# ekomigacz_3R.net
KiCad netlist of a schematic drawn in EAGLE
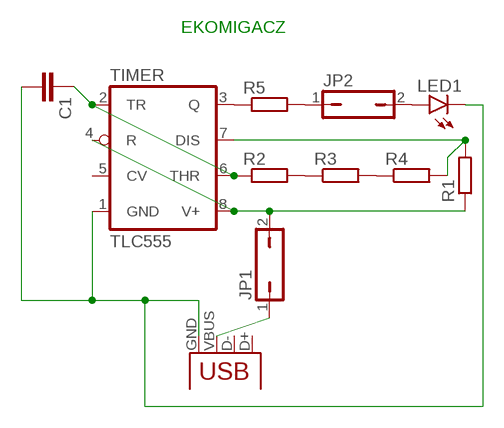
[diagram p0: schematic, sheet 1]

(export (version "E")
  (design (tool "Eeschema 10.0.6"))
  (components
    (comp (ref "C1")
      (value "C5/3")
      (footprint "eagle-import:C5B3")
      (libsource (lib "eagle-import") (part "C5/3"))
    )
    (comp (ref "JP1")
      (value "JP1Q")
      (footprint "eagle-import:JP1")
      (libsource (lib "eagle-import") (part "JP1Q"))
    )
    (comp (ref "JP2")
      (value "JP1Q")
      (footprint "eagle-import:JP1")
      (libsource (lib "eagle-import") (part "JP1Q"))
    )
    (comp (ref "LED1")
      (value "LED5MM")
      (footprint "eagle-import:LED5MM")
      (libsource (lib "eagle-import") (part "LED5MM"))
    )
    (comp (ref "R1")
      (value "R-EU_0207/10")
      (footprint "eagle-import:0207_10")
      (libsource (lib "eagle-import") (part "R-EU_0207/10"))
    )
    (comp (ref "R2")
      (value "R-EU_0207/10")
      (footprint "eagle-import:0207_10")
      (libsource (lib "eagle-import") (part "R-EU_0207/10"))
    )
    (comp (ref "R3")
      (value "R-EU_0207/10")
      (footprint "eagle-import:0207_10")
      (libsource (lib "eagle-import") (part "R-EU_0207/10"))
    )
    (comp (ref "R4")
      (value "R-EU_0207/10")
      (footprint "eagle-import:0207_10")
      (libsource (lib "eagle-import") (part "R-EU_0207/10"))
    )
    (comp (ref "R5")
      (value "R-EU_0207/10")
      (footprint "eagle-import:0207_10")
      (libsource (lib "eagle-import") (part "R-EU_0207/10"))
    )
    (comp (ref "TIMER")
      (value "TLC555")
      (footprint "eagle-import:DIL08")
      (fields (field (name "SPICEPREFIX") "X"))
      (libsource (lib "eagle-import") (part "555NNE"))
    )
    (comp (ref "X1")
      (value "USB-A-H")
      (footprint "eagle-import:USB-A-H")
      (libsource (lib "eagle-import") (part "USB-A-H"))
    )
  )
  (nets
    (net (code "1") (name "Net-(JP1-Pad1)") (class "Default")
      (node (ref "JP1") (pin "1") (pinfunction "1_1") (pintype "passive"))
      (node (ref "X1") (pin "VBUS") (pinfunction "VBUS_VBUS") (pintype "bidirectional"))
    )
    (net (code "2") (name "Net-(JP2-Pad1)") (class "Default")
      (node (ref "JP2") (pin "1") (pinfunction "1_1") (pintype "passive"))
      (node (ref "R5") (pin "2") (pinfunction "2_2") (pintype "passive"))
    )
    (net (code "3") (name "Net-(JP2-Pad2)") (class "Default")
      (node (ref "JP2") (pin "2") (pinfunction "2_2") (pintype "passive"))
      (node (ref "LED1") (pin "A") (pinfunction "A_A") (pintype "passive"))
    )
    (net (code "4") (name "Net-(LED1-C)") (class "Default")
      (node (ref "C1") (pin "2") (pinfunction "2_2") (pintype "passive"))
      (node (ref "LED1") (pin "K") (pinfunction "C_K") (pintype "passive"))
      (node (ref "TIMER") (pin "1") (pinfunction "GND_1") (pintype "power_in"))
      (node (ref "X1") (pin "GND") (pinfunction "GND_GND") (pintype "bidirectional"))
    )
    (net (code "5") (name "Net-(R2-Pad2)") (class "Default")
      (node (ref "R2") (pin "2") (pinfunction "2_2") (pintype "passive"))
      (node (ref "R3") (pin "1") (pinfunction "1_1") (pintype "passive"))
    )
    (net (code "6") (name "Net-(R3-Pad2)") (class "Default")
      (node (ref "R3") (pin "2") (pinfunction "2_2") (pintype "passive"))
      (node (ref "R4") (pin "1") (pinfunction "1_1") (pintype "passive"))
    )
    (net (code "7") (name "Net-(TIMER-DIS)") (class "Default")
      (node (ref "R1") (pin "2") (pinfunction "2_2") (pintype "passive"))
      (node (ref "R4") (pin "2") (pinfunction "2_2") (pintype "passive"))
      (node (ref "TIMER") (pin "7") (pinfunction "DIS_7") (pintype "input"))
    )
    (net (code "8") (name "Net-(TIMER-Q)") (class "Default")
      (node (ref "R5") (pin "1") (pinfunction "1_1") (pintype "passive"))
      (node (ref "TIMER") (pin "3") (pinfunction "Q_3") (pintype "output"))
    )
    (net (code "9") (name "Net-(TIMER-R)") (class "Default")
      (node (ref "JP1") (pin "2") (pinfunction "2_2") (pintype "passive"))
      (node (ref "R1") (pin "1") (pinfunction "1_1") (pintype "passive"))
      (node (ref "TIMER") (pin "4") (pinfunction "R_4") (pintype "input"))
      (node (ref "TIMER") (pin "8") (pinfunction "V+_8") (pintype "power_in"))
    )
    (net (code "10") (name "Net-(TIMER-THR)") (class "Default")
      (node (ref "C1") (pin "1") (pinfunction "1_1") (pintype "passive"))
      (node (ref "R2") (pin "1") (pinfunction "1_1") (pintype "passive"))
      (node (ref "TIMER") (pin "2") (pinfunction "TR_2") (pintype "input"))
      (node (ref "TIMER") (pin "6") (pinfunction "THR_6") (pintype "input"))
    )
    (net (code "11") (name "unconnected-(TIMER-CV-Pad5)") (class "Default")
      (node (ref "TIMER") (pin "5") (pinfunction "CV_5") (pintype "input"))
    )
    (net (code "12") (name "unconnected-(X1-PadD+)") (class "Default")
      (node (ref "X1") (pin "D+") (pinfunction "D+_D+") (pintype "bidirectional"))
    )
    (net (code "13") (name "unconnected-(X1-PadD-)") (class "Default")
      (node (ref "X1") (pin "D-") (pinfunction "D-_D-") (pintype "bidirectional"))
    )
  )
)
